# processingModule.net
KiCad netlist of a schematic drawn in Altium Designer
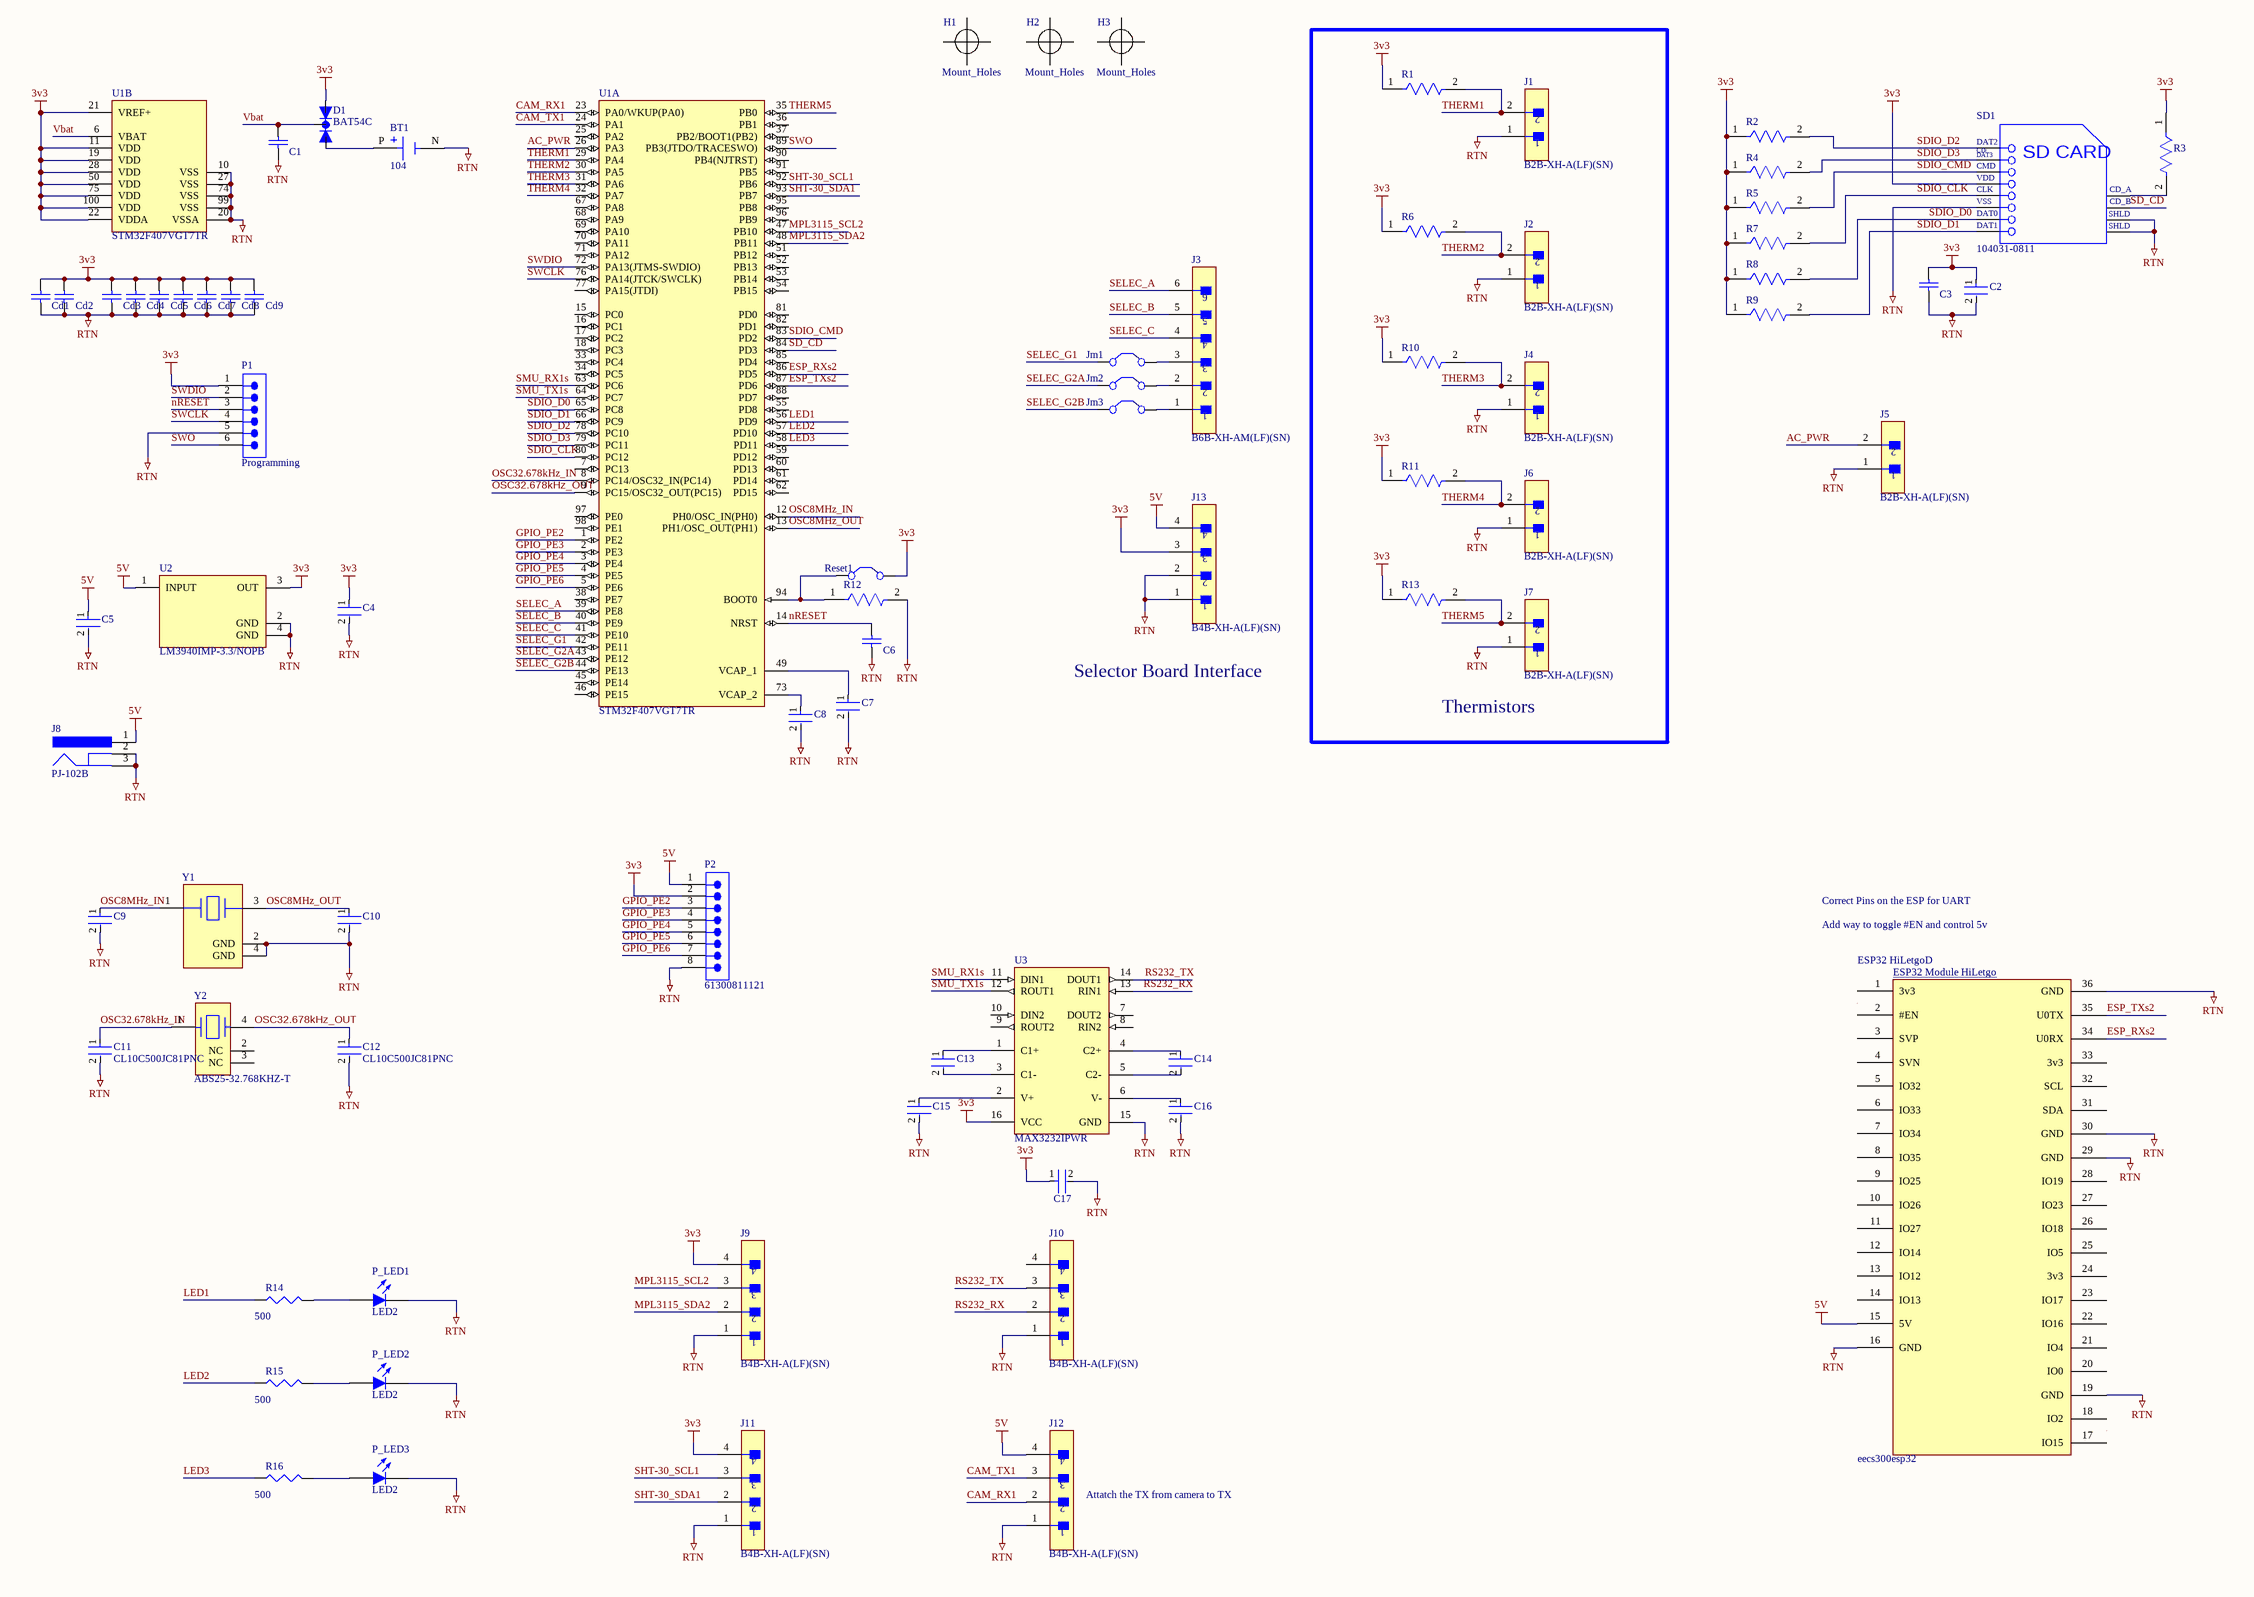
[diagram p0: processingModule.SchDoc]

(export (version "E")
  (design (tool "Eeschema 10.0.6"))
  (components
    (comp (ref "BT1") (value "104") (footprint "BAT_104") (libsource (lib "104") (part "104")))
    (comp (ref "C1")
      (value "CAP 10uF 10V 0603(1608)")
      (footprint "CAPC0603(1608)100_N")
      (description "CAP 10uF 10V ±10% 0603 (1608 Metric) Thickness 1mm SMD")
      (fields (field (name "TOLERANCE") "±10%"))
      (libsource (lib "Altium Content Vault") (part "CMP-1035-02799-1"))
    )
    (comp (ref "C2")
      (value "C0603X104K5RACTU")
      (footprint "FP-C0603-CJ-MFG")
      (description "CAP CER 0.1UF 50V X7R 0603")
      (fields (field (name "VOLTAGE") "50V") (field (name "MANUFACTURER") "Kemet"))
      (libsource (lib "Altium Content Vault") (part "11868f565c42a9108669ba33697ecf6"))
    )
    (comp (ref "C3")
      (value "CAP 10uF 10V 0603(1608)")
      (footprint "CAPC0603(1608)100_N")
      (description "CAP 10uF 10V ±10% 0603 (1608 Metric) Thickness 1mm SMD")
      (fields (field (name "TOLERANCE") "±10%"))
      (libsource (lib "Altium Content Vault") (part "CMP-1035-02799-1"))
    )
    (comp (ref "C4")
      (value "C2012X5R1A336M125AC")
      (footprint "FP-C2012-125-0_2-IPC_A")
      (description "Multilayer Ceramic Capacitors 33μF ±20% 10V X5R SMD 0805")
      (fields (field (name "TOLERANCE") "20%"))
      (libsource (lib "Altium Content Vault") (part "b4654b650e69147ec39a6b967a45e02"))
    )
    (comp (ref "C5")
      (value "GRM188R71C474KA88D")
      (footprint "FP-GRM188-0_1-e0_2_0_5-IPC_A")
      (description "Chip Multilayer Ceramic Capacitors for General Purpose, 0603, 0.47uF, X7R, 15%, 10%, 16V")
      (fields (field (name "VOLTAGE") "16V") (field (name "TOLERANCE") "10%"))
      (libsource (lib "Altium Content Vault") (part "11868f565c42a9108669ba33697ecf6"))
    )
    (comp (ref "C6")
      (value "CAP 100nF 16V 0603(1608)")
      (footprint "CAPC0603(1608)100_N")
      (description "CAP 100nF 16V ±5% 0603 (1608 Metric) Thickness 1mm SMD")
      (fields (field (name "TOLERANCE") "±5%"))
      (libsource (lib "Altium Content Vault") (part "CMP-1035-02583-1"))
    )
    (comp (ref "C7")
      (value "C0603C225K4PACTU")
      (footprint "FP-C0603C225K4PACTU-MFG")
      (description "CAP CER 2.2UF 16V X5R 0603")
      (fields (field (name "TOLERANCE") "10%") (field (name "VOLTAGE") "16V"))
      (libsource (lib "Altium Content Vault") (part "b4654b650e69147ec39a6b967a45e02"))
    )
    (comp (ref "C8")
      (value "C0603C225K4PACTU")
      (footprint "FP-C0603C225K4PACTU-MFG")
      (description "CAP CER 2.2UF 16V X5R 0603")
      (fields (field (name "TOLERANCE") "10%") (field (name "VOLTAGE") "16V"))
      (libsource (lib "Altium Content Vault") (part "b4654b650e69147ec39a6b967a45e02"))
    )
    (comp (ref "C9")
      (value "C0603C200J5GACTU")
      (footprint "FP-C0603C-CF-MFG")
      (description "CAP CER 20PF 50V 5% NP0 0603")
      (fields
        (field (name "MANUFACTURER") "KEMET")
        (field (name "OCTOPART") "https://octopart.com/c0603c200j5gactu-kemet-9138585")
      )
      (libsource (lib "Altium Content Vault") (part "b4654b650e69147ec39a6b967a45e02"))
    )
    (comp (ref "C10")
      (value "C0603C200J5GACTU")
      (footprint "FP-C0603C-CF-MFG")
      (description "CAP CER 20PF 50V 5% NP0 0603")
      (fields
        (field (name "MANUFACTURER") "KEMET")
        (field (name "OCTOPART") "https://octopart.com/c0603c200j5gactu-kemet-9138585")
      )
      (libsource (lib "Altium Content Vault") (part "b4654b650e69147ec39a6b967a45e02"))
    )
    (comp (ref "C11")
      (value "CL10C500JC81PNC")
      (footprint "FP-CL10-IPC_B")
      (description "Cap Ceramic 50pF 100V C0G ±5% Pad SMD 0603 +125°C T/R")
      (fields (field (name "TOLERANCE") "5%"))
      (libsource (lib "Altium Content Vault") (part "b4654b650e69147ec39a6b967a45e02"))
    )
    (comp (ref "C12")
      (value "CL10C500JC81PNC")
      (footprint "FP-CL10-IPC_B")
      (description "Cap Ceramic 50pF 100V C0G ±5% Pad SMD 0603 +125°C T/R")
      (fields (field (name "TOLERANCE") "5%"))
      (libsource (lib "Altium Content Vault") (part "b4654b650e69147ec39a6b967a45e02"))
    )
    (comp (ref "C13")
      (value "C0603X104K5RACTU")
      (footprint "FP-C0603-CJ-MFG")
      (description "CAP CER 0.1UF 50V X7R 0603")
      (fields (field (name "VOLTAGE") "50V") (field (name "MANUFACTURER") "Kemet"))
      (libsource (lib "Altium Content Vault") (part "11868f565c42a9108669ba33697ecf6"))
    )
    (comp (ref "C14")
      (value "C0603X104K5RACTU")
      (footprint "FP-C0603-CJ-MFG")
      (description "CAP CER 0.1UF 50V X7R 0603")
      (fields (field (name "VOLTAGE") "50V") (field (name "MANUFACTURER") "Kemet"))
      (libsource (lib "Altium Content Vault") (part "11868f565c42a9108669ba33697ecf6"))
    )
    (comp (ref "C15")
      (value "C0603X104K5RACTU")
      (footprint "FP-C0603-CJ-MFG")
      (description "CAP CER 0.1UF 50V X7R 0603")
      (fields (field (name "VOLTAGE") "50V") (field (name "MANUFACTURER") "Kemet"))
      (libsource (lib "Altium Content Vault") (part "11868f565c42a9108669ba33697ecf6"))
    )
    (comp (ref "C16")
      (value "C0603X104K5RACTU")
      (footprint "FP-C0603-CJ-MFG")
      (description "CAP CER 0.1UF 50V X7R 0603")
      (fields (field (name "VOLTAGE") "50V") (field (name "MANUFACTURER") "Kemet"))
      (libsource (lib "Altium Content Vault") (part "11868f565c42a9108669ba33697ecf6"))
    )
    (comp (ref "C17")
      (value "C0603X104K5RACTU")
      (footprint "FP-C0603-CJ-MFG")
      (description "CAP CER 0.1UF 50V X7R 0603")
      (fields (field (name "VOLTAGE") "50V") (field (name "MANUFACTURER") "Kemet"))
      (libsource (lib "Altium Content Vault") (part "11868f565c42a9108669ba33697ecf6"))
    )
    (comp (ref "Cd1")
      (value "CAP 10uF 10V 0603(1608)")
      (footprint "CAPC0603(1608)100_N")
      (description "CAP 10uF 10V ±10% 0603 (1608 Metric) Thickness 1mm SMD")
      (fields (field (name "TOLERANCE") "±10%"))
      (libsource (lib "Altium Content Vault") (part "CMP-1035-02799-1"))
    )
    (comp (ref "Cd2")
      (value "CAP 10uF 10V 0603(1608)")
      (footprint "CAPC0603(1608)100_N")
      (description "CAP 10uF 10V ±10% 0603 (1608 Metric) Thickness 1mm SMD")
      (fields (field (name "TOLERANCE") "±10%"))
      (libsource (lib "Altium Content Vault") (part "CMP-1035-02799-1"))
    )
    (comp (ref "Cd3")
      (value "CAP 100nF 16V 0603(1608)")
      (footprint "CAPC0603(1608)100_N")
      (description "CAP 100nF 16V ±5% 0603 (1608 Metric) Thickness 1mm SMD")
      (fields (field (name "TOLERANCE") "±5%"))
      (libsource (lib "Altium Content Vault") (part "CMP-1035-02583-1"))
    )
    (comp (ref "Cd4")
      (value "CAP 100nF 16V 0603(1608)")
      (footprint "CAPC0603(1608)100_N")
      (description "CAP 100nF 16V ±5% 0603 (1608 Metric) Thickness 1mm SMD")
      (fields (field (name "TOLERANCE") "±5%"))
      (libsource (lib "Altium Content Vault") (part "CMP-1035-02583-1"))
    )
    (comp (ref "Cd5")
      (value "CAP 100nF 16V 0603(1608)")
      (footprint "CAPC0603(1608)100_N")
      (description "CAP 100nF 16V ±5% 0603 (1608 Metric) Thickness 1mm SMD")
      (fields (field (name "TOLERANCE") "±5%"))
      (libsource (lib "Altium Content Vault") (part "CMP-1035-02583-1"))
    )
    (comp (ref "Cd6")
      (value "CAP 100nF 16V 0603(1608)")
      (footprint "CAPC0603(1608)100_N")
      (description "CAP 100nF 16V ±5% 0603 (1608 Metric) Thickness 1mm SMD")
      (fields (field (name "TOLERANCE") "±5%"))
      (libsource (lib "Altium Content Vault") (part "CMP-1035-02583-1"))
    )
    (comp (ref "Cd7")
      (value "CAP 100nF 16V 0603(1608)")
      (footprint "CAPC0603(1608)100_N")
      (description "CAP 100nF 16V ±5% 0603 (1608 Metric) Thickness 1mm SMD")
      (fields (field (name "TOLERANCE") "±5%"))
      (libsource (lib "Altium Content Vault") (part "CMP-1035-02583-1"))
    )
    (comp (ref "Cd8")
      (value "CAP 100nF 16V 0603(1608)")
      (footprint "CAPC0603(1608)100_N")
      (description "CAP 100nF 16V ±5% 0603 (1608 Metric) Thickness 1mm SMD")
      (fields (field (name "TOLERANCE") "±5%"))
      (libsource (lib "Altium Content Vault") (part "CMP-1035-02583-1"))
    )
    (comp (ref "Cd9")
      (value "CAP 100nF 16V 0603(1608)")
      (footprint "CAPC0603(1608)100_N")
      (description "CAP 100nF 16V ±5% 0603 (1608 Metric) Thickness 1mm SMD")
      (fields (field (name "TOLERANCE") "±5%"))
      (libsource (lib "Altium Content Vault") (part "CMP-1035-02583-1"))
    )
    (comp (ref "D1")
      (value "BAT54C")
      (footprint "SOT23-R")
      (fields (field (name "MF") "ON Semiconductor"))
      (libsource (lib "BAT54C") (part "BAT54C"))
    )
    (comp (ref "ESP32 HiLetgo")
      (value "eecs300esp32")
      (footprint "eecs300esp32-Footprint-1")
      (description "HiLetgo ESP32 knock off")
      (libsource (lib "esp32") (part "CMP-001-0002-3"))
    )
    (comp (ref "H1")
      (value "Mount_Holes")
      (footprint "MountHole-4-40PTH")
      (libsource (lib "SolarCar") (part "Mount_Holes"))
    )
    (comp (ref "H2")
      (value "Mount_Holes")
      (footprint "MountHole-4-40PTH")
      (libsource (lib "SolarCar") (part "Mount_Holes"))
    )
    (comp (ref "H3")
      (value "Mount_Holes")
      (footprint "MountHole-4-40PTH")
      (libsource (lib "SolarCar") (part "Mount_Holes"))
    )
    (comp (ref "J1")
      (value "B2B-XH-A(LF)(SN)")
      (footprint "FP-B2B-XH-A_LF_SN-MFG")
      (description "CONN HEADER VERT 2POS 2.5MM")
      (libsource (lib "Altium Content Vault") (part "3bc925449376181038e59eaffc5286c"))
    )
    (comp (ref "J2")
      (value "B2B-XH-A(LF)(SN)")
      (footprint "FP-B2B-XH-A_LF_SN-MFG")
      (description "CONN HEADER VERT 2POS 2.5MM")
      (libsource (lib "Altium Content Vault") (part "3bc925449376181038e59eaffc5286c"))
    )
    (comp (ref "J3")
      (value "B6B-XH-AM(LF)(SN)")
      (footprint "FP-B6B-XH-AM_LF_SN-MFG")
      (description "CONN HEADER VERT 6POS 2.5MM")
      (libsource (lib "Altium Content Vault") (part "f2cb566baf1c37ab5a3b8e90bbeafd6"))
    )
    (comp (ref "J4")
      (value "B2B-XH-A(LF)(SN)")
      (footprint "FP-B2B-XH-A_LF_SN-MFG")
      (description "CONN HEADER VERT 2POS 2.5MM")
      (libsource (lib "Altium Content Vault") (part "3bc925449376181038e59eaffc5286c"))
    )
    (comp (ref "J5")
      (value "B2B-XH-A(LF)(SN)")
      (footprint "FP-B2B-XH-A_LF_SN-MFG")
      (description "CONN HEADER VERT 2POS 2.5MM")
      (libsource (lib "Altium Content Vault") (part "3bc925449376181038e59eaffc5286c"))
    )
    (comp (ref "J6")
      (value "B2B-XH-A(LF)(SN)")
      (footprint "FP-B2B-XH-A_LF_SN-MFG")
      (description "CONN HEADER VERT 2POS 2.5MM")
      (libsource (lib "Altium Content Vault") (part "3bc925449376181038e59eaffc5286c"))
    )
    (comp (ref "J7")
      (value "B2B-XH-A(LF)(SN)")
      (footprint "FP-B2B-XH-A_LF_SN-MFG")
      (description "CONN HEADER VERT 2POS 2.5MM")
      (libsource (lib "Altium Content Vault") (part "3bc925449376181038e59eaffc5286c"))
    )
    (comp (ref "J8")
      (value "PJ-102B")
      (footprint "CUI-PJ-102B_V")
      (fields (field (name "MANUFACTURER") "CUIInc."))
      (libsource (lib "Altium Content Vault") (part "JACK-2CD3-RN"))
    )
    (comp (ref "J9")
      (value "B4B-XH-A(LF)(SN)")
      (footprint "FP-B4B-XH-A_LF_SN-MFG")
      (description "CONN HEADER VERT 4POS 2.5MM")
      (libsource (lib "Altium Content Vault") (part "299a8cea1bdcbc3624fe62c390fa72c"))
    )
    (comp (ref "J10")
      (value "B4B-XH-A(LF)(SN)")
      (footprint "FP-B4B-XH-A_LF_SN-MFG")
      (description "CONN HEADER VERT 4POS 2.5MM")
      (libsource (lib "Altium Content Vault") (part "299a8cea1bdcbc3624fe62c390fa72c"))
    )
    (comp (ref "J11")
      (value "B4B-XH-A(LF)(SN)")
      (footprint "FP-B4B-XH-A_LF_SN-MFG")
      (description "CONN HEADER VERT 4POS 2.5MM")
      (libsource (lib "Altium Content Vault") (part "299a8cea1bdcbc3624fe62c390fa72c"))
    )
    (comp (ref "J12")
      (value "B4B-XH-A(LF)(SN)")
      (footprint "FP-B4B-XH-A_LF_SN-MFG")
      (description "CONN HEADER VERT 4POS 2.5MM")
      (libsource (lib "Altium Content Vault") (part "299a8cea1bdcbc3624fe62c390fa72c"))
    )
    (comp (ref "J13")
      (value "B4B-XH-A(LF)(SN)")
      (footprint "FP-B4B-XH-A_LF_SN-MFG")
      (description "CONN HEADER VERT 4POS 2.5MM")
      (libsource (lib "Altium Content Vault") (part "299a8cea1bdcbc3624fe62c390fa72c"))
    )
    (comp (ref "Jm1")
      (value "SolderJumper")
      (footprint "bridge")
      (description "Solder Configuration Jumper")
      (fields (field (name "PUBLISHER") "Altium Limited"))
      (libsource (lib "SolarCar") (part "SolderJumper"))
    )
    (comp (ref "Jm2")
      (value "SolderJumper")
      (footprint "bridge")
      (description "Solder Configuration Jumper")
      (fields (field (name "PUBLISHER") "Altium Limited"))
      (libsource (lib "SolarCar") (part "SolderJumper"))
    )
    (comp (ref "Jm3")
      (value "SolderJumper")
      (footprint "bridge")
      (description "Solder Configuration Jumper")
      (fields (field (name "PUBLISHER") "Altium Limited"))
      (libsource (lib "SolarCar") (part "SolderJumper"))
    )
    (comp (ref "P1")
      (value "Programming")
      (footprint "61300611121")
      (libsource (lib "Altium Content Vault") (part "Header_Male_1R_06P"))
    )
    (comp (ref "P2")
      (value "61300811121")
      (footprint "61300811121")
      (libsource (lib "Altium Content Vault") (part "Header_Male_1R_08P"))
    )
    (comp (ref "P_LED1")
      (value "LED2")
      (footprint "LED0805")
      (description "Typical RED, GREEN, YELLOW, AMBER GaAs LED")
      (fields (field (name "PUBLISHER") "Altium Limited"))
      (libsource (lib "University of Michigan Solar Car Team") (part "LED2"))
    )
    (comp (ref "P_LED2")
      (value "LED2")
      (footprint "LED0805")
      (description "Typical RED, GREEN, YELLOW, AMBER GaAs LED")
      (fields (field (name "PUBLISHER") "Altium Limited"))
      (libsource (lib "University of Michigan Solar Car Team") (part "LED2"))
    )
    (comp (ref "P_LED3")
      (value "LED2")
      (footprint "LED0805")
      (description "Typical RED, GREEN, YELLOW, AMBER GaAs LED")
      (fields (field (name "PUBLISHER") "Altium Limited"))
      (libsource (lib "University of Michigan Solar Car Team") (part "LED2"))
    )
    (comp (ref "R1")
      (value "RC0603FR-0710KL")
      (footprint "FP-RC0603-0_55-IPC_C")
      (description "RES 10K OHM 1% 1/10W 0603")
      (fields (field (name "TOLERANCE") "1%"))
      (libsource (lib "Altium Content Vault") (part "1029c3af85768c4190bb7ad29bc67b5"))
    )
    (comp (ref "R2")
      (value "RC0603FR-0747KL")
      (footprint "FP-RC0603FR-0747KL-MFG")
      (description "RES SMD 47K OHM 1% 1/10W 0603")
      (fields (field (name "TOLERANCE") "1%"))
      (libsource (lib "Altium Content Vault") (part "1029c3af85768c4190bb7ad29bc67b5"))
    )
    (comp (ref "R3")
      (value "RC0603FR-0747KL")
      (footprint "FP-RC0603FR-0747KL-MFG")
      (description "RES SMD 47K OHM 1% 1/10W 0603")
      (fields (field (name "TOLERANCE") "1%"))
      (libsource (lib "Altium Content Vault") (part "1029c3af85768c4190bb7ad29bc67b5"))
    )
    (comp (ref "R4")
      (value "RC0603FR-0747KL")
      (footprint "FP-RC0603FR-0747KL-MFG")
      (description "RES SMD 47K OHM 1% 1/10W 0603")
      (fields (field (name "TOLERANCE") "1%"))
      (libsource (lib "Altium Content Vault") (part "1029c3af85768c4190bb7ad29bc67b5"))
    )
    (comp (ref "R5")
      (value "RC0603FR-0747KL")
      (footprint "FP-RC0603FR-0747KL-MFG")
      (description "RES SMD 47K OHM 1% 1/10W 0603")
      (fields (field (name "TOLERANCE") "1%"))
      (libsource (lib "Altium Content Vault") (part "1029c3af85768c4190bb7ad29bc67b5"))
    )
    (comp (ref "R6")
      (value "RC0603FR-0710KL")
      (footprint "FP-RC0603-0_55-IPC_C")
      (description "RES 10K OHM 1% 1/10W 0603")
      (fields (field (name "TOLERANCE") "1%"))
      (libsource (lib "Altium Content Vault") (part "1029c3af85768c4190bb7ad29bc67b5"))
    )
    (comp (ref "R7")
      (value "RC0603FR-0747KL")
      (footprint "FP-RC0603FR-0747KL-MFG")
      (description "RES SMD 47K OHM 1% 1/10W 0603")
      (fields (field (name "TOLERANCE") "1%"))
      (libsource (lib "Altium Content Vault") (part "1029c3af85768c4190bb7ad29bc67b5"))
    )
    (comp (ref "R8")
      (value "RC0603FR-0747KL")
      (footprint "FP-RC0603FR-0747KL-MFG")
      (description "RES SMD 47K OHM 1% 1/10W 0603")
      (fields (field (name "TOLERANCE") "1%"))
      (libsource (lib "Altium Content Vault") (part "1029c3af85768c4190bb7ad29bc67b5"))
    )
    (comp (ref "R9")
      (value "RC0603FR-0747KL")
      (footprint "FP-RC0603FR-0747KL-MFG")
      (description "RES SMD 47K OHM 1% 1/10W 0603")
      (fields (field (name "TOLERANCE") "1%"))
      (libsource (lib "Altium Content Vault") (part "1029c3af85768c4190bb7ad29bc67b5"))
    )
    (comp (ref "R10")
      (value "RC0603FR-0710KL")
      (footprint "FP-RC0603-0_55-IPC_C")
      (description "RES 10K OHM 1% 1/10W 0603")
      (fields (field (name "TOLERANCE") "1%"))
      (libsource (lib "Altium Content Vault") (part "1029c3af85768c4190bb7ad29bc67b5"))
    )
    (comp (ref "R11")
      (value "RC0603FR-0710KL")
      (footprint "FP-RC0603-0_55-IPC_C")
      (description "RES 10K OHM 1% 1/10W 0603")
      (fields (field (name "TOLERANCE") "1%"))
      (libsource (lib "Altium Content Vault") (part "1029c3af85768c4190bb7ad29bc67b5"))
    )
    (comp (ref "R12")
      (value "RC0603FR-0710KL")
      (footprint "FP-RC0603-0_55-IPC_C")
      (description "RES 10K OHM 1% 1/10W 0603")
      (fields (field (name "TOLERANCE") "1%"))
      (libsource (lib "Altium Content Vault") (part "1029c3af85768c4190bb7ad29bc67b5"))
    )
    (comp (ref "R13")
      (value "RC0603FR-0710KL")
      (footprint "FP-RC0603-0_55-IPC_C")
      (description "RES 10K OHM 1% 1/10W 0603")
      (fields (field (name "TOLERANCE") "1%"))
      (libsource (lib "Altium Content Vault") (part "1029c3af85768c4190bb7ad29bc67b5"))
    )
    (comp (ref "R14")
      (value "500")
      (footprint "J1-0603")
      (description "Resistor")
      (fields (field (name "PUBLISHER") "Altium Limited"))
      (libsource (lib "SolarCar") (part "Res3"))
    )
    (comp (ref "R15")
      (value "500")
      (footprint "J1-0603")
      (description "Resistor")
      (fields (field (name "PUBLISHER") "Altium Limited"))
      (libsource (lib "SolarCar") (part "Res3"))
    )
    (comp (ref "R16")
      (value "500")
      (footprint "J1-0603")
      (description "Resistor")
      (fields (field (name "PUBLISHER") "Altium Limited"))
      (libsource (lib "SolarCar") (part "Res3"))
    )
    (comp (ref "Reset1")
      (value "SolderJumper")
      (footprint "bridge")
      (description "Solder Configuration Jumper")
      (fields (field (name "PUBLISHER") "Altium Limited"))
      (libsource (lib "SolarCar") (part "SolderJumper"))
    )
    (comp (ref "SD1")
      (value "104031-0811")
      (footprint "MOLX-104031-0811_V")
      (description "Micro SD Card, RA, -25 to 85 degC, 8-Pin SMD, RoHS, Tape and Reel")
      (fields (field (name "MANUFACTURER") "Molex"))
      (libsource (lib "Altium Content Vault") (part "CN-SD-8-2SW-2S"))
    )
    (comp (ref "U1")
      (value "STM32F407VGT7TR")
      (footprint "STM-LQFP100_L")
      (libsource (lib "Altium Content Vault") (part "MC-ARM-STM32F4XX-LQFP100"))
    )
    (comp (ref "U2")
      (value "LM3940IMP-3.3/NOPB")
      (footprint "FP-DCY0004A-MFG")
      (description "IC REG LINEAR 3.3V 1A SOT223-4")
      (libsource (lib "Altium Content Vault") (part "ef78896361455d16e3252a05c23564e"))
    )
    (comp (ref "U3")
      (value "MAX3232IPWR")
      (footprint "PW0016A_N")
      (libsource (lib "Altium Content Vault") (part "TI-MAX3232-TSSOP_PW-16"))
    )
    (comp (ref "Y1")
      (value "ABM3B-8.000MHZ-10-D-1-G-T")
      (footprint "FP-ABM3B-MFG")
      (description "Crystal 8MHz ±10ppm 10pF SMD-4 5mm x 3.2mm")
      (libsource (lib "Altium Content Vault") (part "48e526d86b7f2615d98721063c72f49"))
    )
    (comp (ref "Y2")
      (value "ABS25-32.768KHZ-T")
      (footprint "FP-ABS25-MFG")
      (description "CRYSTAL 32.7680KHZ 12.5PF SMD")
      (fields (field (name "TOLERANCE") "20ppm"))
      (libsource (lib "Altium Content Vault") (part "d2378e42ab3755ffcd472789242ec61"))
    )
  )
  (nets
    (net (code "1") (name "/AC_PWR") (class "Default")
      (node (ref "J5") (pin "2") (pinfunction "2_2") (pintype "passive"))
      (node (ref "U1") (pin "26") (pinfunction "PA3_26") (pintype "bidirectional"))
    )
    (net (code "2") (name "/CAM_RX1") (class "Default")
      (node (ref "J12") (pin "2") (pinfunction "2_2") (pintype "passive"))
      (node (ref "U1") (pin "23") (pinfunction "PA0/WKUP(PA0)_23") (pintype "bidirectional"))
    )
    (net (code "3") (name "/CAM_TX1") (class "Default")
      (node (ref "J12") (pin "3") (pinfunction "3_3") (pintype "passive"))
      (node (ref "U1") (pin "24") (pinfunction "PA1_24") (pintype "bidirectional"))
    )
    (net (code "4") (name "/ESP_RXs2") (class "Default")
      (node (ref "ESP32 HiLetgo") (pin "34") (pinfunction "U0RX_34") (pintype "passive"))
      (node (ref "U1") (pin "86") (pinfunction "PD5_86") (pintype "bidirectional"))
    )
    (net (code "5") (name "/ESP_TXs2") (class "Default")
      (node (ref "ESP32 HiLetgo") (pin "35") (pinfunction "U0TX_35") (pintype "passive"))
      (node (ref "U1") (pin "87") (pinfunction "PD6_87") (pintype "bidirectional"))
    )
    (net (code "6") (name "/GPIO_PE2") (class "Default")
      (node (ref "P2") (pin "3") (pinfunction "3_3") (pintype "passive"))
      (node (ref "U1") (pin "1") (pinfunction "PE2_1") (pintype "bidirectional"))
    )
    (net (code "7") (name "/GPIO_PE3") (class "Default")
      (node (ref "P2") (pin "4") (pinfunction "4_4") (pintype "passive"))
      (node (ref "U1") (pin "2") (pinfunction "PE3_2") (pintype "bidirectional"))
    )
    (net (code "8") (name "/GPIO_PE4") (class "Default")
      (node (ref "P2") (pin "5") (pinfunction "5_5") (pintype "passive"))
      (node (ref "U1") (pin "3") (pinfunction "PE4_3") (pintype "bidirectional"))
    )
    (net (code "9") (name "/GPIO_PE5") (class "Default")
      (node (ref "P2") (pin "6") (pinfunction "6_6") (pintype "passive"))
      (node (ref "U1") (pin "4") (pinfunction "PE5_4") (pintype "bidirectional"))
    )
    (net (code "10") (name "/GPIO_PE6") (class "Default")
      (node (ref "P2") (pin "7") (pinfunction "7_7") (pintype "passive"))
      (node (ref "U1") (pin "5") (pinfunction "PE6_5") (pintype "bidirectional"))
    )
    (net (code "11") (name "/LED1") (class "Default")
      (node (ref "R14") (pin "1") (pinfunction "1_1") (pintype "passive"))
      (node (ref "U1") (pin "56") (pinfunction "PD9_56") (pintype "bidirectional"))
    )
    (net (code "12") (name "/LED2") (class "Default")
      (node (ref "R15") (pin "1") (pinfunction "1_1") (pintype "passive"))
      (node (ref "U1") (pin "57") (pinfunction "PD10_57") (pintype "bidirectional"))
    )
    (net (code "13") (name "/LED3") (class "Default")
      (node (ref "R16") (pin "1") (pinfunction "1_1") (pintype "passive"))
      (node (ref "U1") (pin "58") (pinfunction "PD11_58") (pintype "bidirectional"))
    )
    (net (code "14") (name "/MPL3115_SCL2") (class "Default")
      (node (ref "J9") (pin "3") (pinfunction "3_3") (pintype "passive"))
      (node (ref "U1") (pin "47") (pinfunction "PB10_47") (pintype "bidirectional"))
    )
    (net (code "15") (name "/MPL3115_SDA2") (class "Default")
      (node (ref "J9") (pin "2") (pinfunction "2_2") (pintype "passive"))
      (node (ref "U1") (pin "48") (pinfunction "PB11_48") (pintype "bidirectional"))
    )
    (net (code "16") (name "/OSC8MHz_IN") (class "Default")
      (node (ref "C9") (pin "1") (pinfunction "1_1") (pintype "passive"))
      (node (ref "U1") (pin "12") (pinfunction "PH0/OSC_IN(PH0)_12") (pintype "bidirectional"))
      (node (ref "Y1") (pin "1") (pinfunction "1_1") (pintype "passive"))
    )
    (net (code "17") (name "/OSC8MHz_OUT") (class "Default")
      (node (ref "C10") (pin "1") (pinfunction "1_1") (pintype "passive"))
      (node (ref "U1") (pin "13") (pinfunction "PH1/OSC_OUT(PH1)_13") (pintype "bidirectional"))
      (node (ref "Y1") (pin "3") (pinfunction "3_3") (pintype "passive"))
    )
    (net (code "18") (name "/OSC32.678kHz_IN") (class "Default")
      (node (ref "C11") (pin "1") (pinfunction "1_1") (pintype "passive"))
      (node (ref "U1") (pin "8") (pinfunction "PC14/OSC32_IN(PC14)_8") (pintype "bidirectional"))
      (node (ref "Y2") (pin "1") (pinfunction "1_1") (pintype "passive"))
    )
    (net (code "19") (name "/OSC32.678kHz_OUT") (class "Default")
      (node (ref "C12") (pin "1") (pinfunction "1_1") (pintype "passive"))
      (node (ref "U1") (pin "9") (pinfunction "PC15/OSC32_OUT(PC15)_9") (pintype "bidirectional"))
      (node (ref "Y2") (pin "4") (pinfunction "4_4") (pintype "passive"))
    )
    (net (code "20") (name "/RS232_RX") (class "Default")
      (node (ref "J10") (pin "2") (pinfunction "2_2") (pintype "passive"))
      (node (ref "U3") (pin "13") (pinfunction "RIN1_13") (pintype "input"))
    )
    (net (code "21") (name "/RS232_TX") (class "Default")
      (node (ref "J10") (pin "3") (pinfunction "3_3") (pintype "passive"))
      (node (ref "U3") (pin "14") (pinfunction "DOUT1_14") (pintype "output"))
    )
    (net (code "22") (name "/SDIO_CLK") (class "Default")
      (node (ref "R7") (pin "2") (pinfunction "2_2") (pintype "passive"))
      (node (ref "SD1") (pin "5") (pinfunction "CLK_5") (pintype "passive"))
      (node (ref "U1") (pin "80") (pinfunction "PC12_80") (pintype "bidirectional"))
    )
    (net (code "23") (name "/SDIO_CMD") (class "Default")
      (node (ref "R5") (pin "2") (pinfunction "2_2") (pintype "passive"))
      (node (ref "SD1") (pin "3") (pinfunction "VSS1_3") (pintype "passive"))
      (node (ref "U1") (pin "83") (pinfunction "PD2_83") (pintype "bidirectional"))
    )
    (net (code "24") (name "/SDIO_D0") (class "Default")
      (node (ref "R8") (pin "2") (pinfunction "2_2") (pintype "passive"))
      (node (ref "SD1") (pin "7") (pinfunction "DAT0_7") (pintype "passive"))
      (node (ref "U1") (pin "65") (pinfunction "PC8_65") (pintype "bidirectional"))
    )
    (net (code "25") (name "/SDIO_D1") (class "Default")
      (node (ref "R9") (pin "2") (pinfunction "2_2") (pintype "passive"))
      (node (ref "SD1") (pin "8") (pinfunction "DAT1_8") (pintype "passive"))
      (node (ref "U1") (pin "66") (pinfunction "PC9_66") (pintype "bidirectional"))
    )
    (net (code "26") (name "/SDIO_D2") (class "Default")
      (node (ref "R2") (pin "2") (pinfunction "2_2") (pintype "passive"))
      (node (ref "SD1") (pin "1") (pinfunction "CD/DAT3_1") (pintype "passive"))
      (node (ref "U1") (pin "78") (pinfunction "PC10_78") (pintype "bidirectional"))
    )
    (net (code "27") (name "/SDIO_D3") (class "Default")
      (node (ref "R4") (pin "2") (pinfunction "2_2") (pintype "passive"))
      (node (ref "SD1") (pin "2") (pinfunction "CMD_2") (pintype "passive"))
      (node (ref "U1") (pin "79") (pinfunction "PC11_79") (pintype "bidirectional"))
    )
    (net (code "28") (name "/SD_CD") (class "Default")
      (node (ref "SD1") (pin "10") (pinfunction "CD_B_10") (pintype "passive"))
      (node (ref "U1") (pin "84") (pinfunction "PD3_84") (pintype "bidirectional"))
    )
    (net (code "29") (name "/SELEC_A") (class "Default")
      (node (ref "J3") (pin "6") (pinfunction "6_6") (pintype "passive"))
      (node (ref "U1") (pin "39") (pinfunction "PE8_39") (pintype "bidirectional"))
    )
    (net (code "30") (name "/SELEC_B") (class "Default")
      (node (ref "J3") (pin "5") (pinfunction "5_5") (pintype "passive"))
      (node (ref "U1") (pin "40") (pinfunction "PE9_40") (pintype "bidirectional"))
    )
    (net (code "31") (name "/SELEC_C") (class "Default")
      (node (ref "J3") (pin "4") (pinfunction "4_4") (pintype "passive"))
      (node (ref "U1") (pin "41") (pinfunction "PE10_41") (pintype "bidirectional"))
    )
    (net (code "32") (name "/SELEC_G1") (class "Default")
      (node (ref "Jm1") (pin "1") (pinfunction "C1_1") (pintype "passive"))
      (node (ref "U1") (pin "42") (pinfunction "PE11_42") (pintype "bidirectional"))
    )
    (net (code "33") (name "/SELEC_G2A") (class "Default")
      (node (ref "Jm2") (pin "1") (pinfunction "C1_1") (pintype "passive"))
      (node (ref "U1") (pin "43") (pinfunction "PE12_43") (pintype "bidirectional"))
    )
    (net (code "34") (name "/SELEC_G2B") (class "Default")
      (node (ref "Jm3") (pin "1") (pinfunction "C1_1") (pintype "passive"))
      (node (ref "U1") (pin "44") (pinfunction "PE13_44") (pintype "bidirectional"))
    )
    (net (code "35") (name "/SHT-30_SCL1") (class "Default")
      (node (ref "J11") (pin "3") (pinfunction "3_3") (pintype "passive"))
      (node (ref "U1") (pin "92") (pinfunction "PB6_92") (pintype "bidirectional"))
    )
    (net (code "36") (name "/SHT-30_SDA1") (class "Default")
      (node (ref "J11") (pin "2") (pinfunction "2_2") (pintype "passive"))
      (node (ref "U1") (pin "93") (pinfunction "PB7_93") (pintype "bidirectional"))
    )
    (net (code "37") (name "/SMU_RX1s") (class "Default")
      (node (ref "U1") (pin "63") (pinfunction "PC6_63") (pintype "bidirectional"))
      (node (ref "U3") (pin "11") (pinfunction "DIN1_11") (pintype "input"))
    )
    (net (code "38") (name "/SMU_TX1s") (class "Default")
      (node (ref "U1") (pin "64") (pinfunction "PC7_64") (pintype "bidirectional"))
      (node (ref "U3") (pin "12") (pinfunction "ROUT1_12") (pintype "output"))
    )
    (net (code "39") (name "/SWCLK") (class "Default")
      (node (ref "P1") (pin "4") (pinfunction "4_4") (pintype "passive"))
      (node (ref "U1") (pin "76") (pinfunction "PA14(JTCK/SWCLK)_76") (pintype "bidirectional"))
    )
    (net (code "40") (name "/SWDIO") (class "Default")
      (node (ref "P1") (pin "2") (pinfunction "2_2") (pintype "passive"))
      (node (ref "U1") (pin "72") (pinfunction "PA13(JTMS-SWDIO)_72") (pintype "bidirectional"))
    )
    (net (code "41") (name "/SWO") (class "Default")
      (node (ref "P1") (pin "6") (pinfunction "6_6") (pintype "passive"))
      (node (ref "U1") (pin "89") (pinfunction "PB3(JTDO/TRACESWO)_89") (pintype "bidirectional"))
    )
    (net (code "42") (name "/THERM1") (class "Default")
      (node (ref "J1") (pin "2") (pinfunction "2_2") (pintype "passive"))
      (node (ref "R1") (pin "2") (pinfunction "2_2") (pintype "passive"))
      (node (ref "U1") (pin "29") (pinfunction "PA4_29") (pintype "bidirectional"))
    )
    (net (code "43") (name "/THERM2") (class "Default")
      (node (ref "J2") (pin "2") (pinfunction "2_2") (pintype "passive"))
      (node (ref "R6") (pin "2") (pinfunction "2_2") (pintype "passive"))
      (node (ref "U1") (pin "30") (pinfunction "PA5_30") (pintype "bidirectional"))
    )
    (net (code "44") (name "/THERM3") (class "Default")
      (node (ref "J4") (pin "2") (pinfunction "2_2") (pintype "passive"))
      (node (ref "R10") (pin "2") (pinfunction "2_2") (pintype "passive"))
      (node (ref "U1") (pin "31") (pinfunction "PA6_31") (pintype "bidirectional"))
    )
    (net (code "45") (name "/THERM4") (class "Default")
      (node (ref "J6") (pin "2") (pinfunction "2_2") (pintype "passive"))
      (node (ref "R11") (pin "2") (pinfunction "2_2") (pintype "passive"))
      (node (ref "U1") (pin "32") (pinfunction "PA7_32") (pintype "bidirectional"))
    )
    (net (code "46") (name "/THERM5") (class "Default")
      (node (ref "J7") (pin "2") (pinfunction "2_2") (pintype "passive"))
      (node (ref "R13") (pin "2") (pinfunction "2_2") (pintype "passive"))
      (node (ref "U1") (pin "35") (pinfunction "PB0_35") (pintype "bidirectional"))
    )
    (net (code "47") (name "/Vbat") (class "Default")
      (node (ref "C1") (pin "2") (pinfunction "2_2") (pintype "passive"))
      (node (ref "D1") (pin "3") (pinfunction "C_3") (pintype "passive"))
      (node (ref "U1") (pin "6") (pinfunction "VBAT_6") (pintype "power_in"))
    )
    (net (code "48") (name "/nRESET") (class "Default")
      (node (ref "C6") (pin "2") (pinfunction "2_2") (pintype "passive"))
      (node (ref "P1") (pin "3") (pinfunction "3_3") (pintype "passive"))
      (node (ref "U1") (pin "14") (pinfunction "NRST_14") (pintype "bidirectional"))
    )
    (net (code "49") (name "3v3") (class "Default")
      (node (ref "C17") (pin "1") (pinfunction "1_1") (pintype "passive"))
      (node (ref "C2") (pin "1") (pinfunction "1_1") (pintype "passive"))
      (node (ref "C3") (pin "2") (pinfunction "2_2") (pintype "passive"))
      (node (ref "C4") (pin "1") (pinfunction "1_1") (pintype "passive"))
      (node (ref "Cd1") (pin "2") (pinfunction "2_2") (pintype "passive"))
      (node (ref "Cd2") (pin "2") (pinfunction "2_2") (pintype "passive"))
      (node (ref "Cd3") (pin "2") (pinfunction "2_2") (pintype "passive"))
      (node (ref "Cd4") (pin "2") (pinfunction "2_2") (pintype "passive"))
      (node (ref "Cd5") (pin "2") (pinfunction "2_2") (pintype "passive"))
      (node (ref "Cd6") (pin "2") (pinfunction "2_2") (pintype "passive"))
      (node (ref "Cd7") (pin "2") (pinfunction "2_2") (pintype "passive"))
      (node (ref "Cd8") (pin "2") (pinfunction "2_2") (pintype "passive"))
      (node (ref "Cd9") (pin "2") (pinfunction "2_2") (pintype "passive"))
      (node (ref "D1") (pin "2") (pinfunction "A2_2") (pintype "passive"))
      (node (ref "J11") (pin "4") (pinfunction "4_4") (pintype "passive"))
      (node (ref "J13") (pin "3") (pinfunction "3_3") (pintype "passive"))
      (node (ref "J9") (pin "4") (pinfunction "4_4") (pintype "passive"))
      (node (ref "P1") (pin "1") (pinfunction "1_1") (pintype "passive"))
      (node (ref "P2") (pin "2") (pinfunction "2_2") (pintype "passive"))
      (node (ref "R1") (pin "1") (pinfunction "1_1") (pintype "passive"))
      (node (ref "R10") (pin "1") (pinfunction "1_1") (pintype "passive"))
      (node (ref "R11") (pin "1") (pinfunction "1_1") (pintype "passive"))
      (node (ref "R13") (pin "1") (pinfunction "1_1") (pintype "passive"))
      (node (ref "R2") (pin "1") (pinfunction "1_1") (pintype "passive"))
      (node (ref "R3") (pin "1") (pinfunction "1_1") (pintype "passive"))
      (node (ref "R4") (pin "1") (pinfunction "1_1") (pintype "passive"))
      (node (ref "R5") (pin "1") (pinfunction "1_1") (pintype "passive"))
      (node (ref "R6") (pin "1") (pinfunction "1_1") (pintype "passive"))
      (node (ref "R7") (pin "1") (pinfunction "1_1") (pintype "passive"))
      (node (ref "R8") (pin "1") (pinfunction "1_1") (pintype "passive"))
      (node (ref "R9") (pin "1") (pinfunction "1_1") (pintype "passive"))
      (node (ref "Reset1") (pin "2") (pinfunction "C2_2") (pintype "passive"))
      (node (ref "SD1") (pin "4") (pinfunction "VDD_4") (pintype "passive"))
      (node (ref "U1") (pin "100") (pinfunction "VDD_100") (pintype "power_in"))
      (node (ref "U1") (pin "11") (pinfunction "VDD_11") (pintype "power_in"))
      (node (ref "U1") (pin "19") (pinfunction "VDD_19") (pintype "power_in"))
      (node (ref "U1") (pin "21") (pinfunction "VREF+_21") (pintype "power_in"))
      (node (ref "U1") (pin "22") (pinfunction "VDDA_22") (pintype "power_in"))
      (node (ref "U1") (pin "28") (pinfunction "VDD_28") (pintype "power_in"))
      (node (ref "U1") (pin "50") (pinfunction "VDD_50") (pintype "power_in"))
      (node (ref "U1") (pin "75") (pinfunction "VDD_75") (pintype "power_in"))
      (node (ref "U2") (pin "3") (pinfunction "OUT_3") (pintype "power_in"))
      (node (ref "U3") (pin "16") (pinfunction "VCC_16") (pintype "power_in"))
    )
    (net (code "50") (name "5V") (class "Default")
      (node (ref "C5") (pin "1") (pinfunction "1_1") (pintype "passive"))
      (node (ref "ESP32 HiLetgo") (pin "15") (pinfunction "5V_15") (pintype "passive"))
      (node (ref "J12") (pin "4") (pinfunction "4_4") (pintype "passive"))
      (node (ref "J13") (pin "4") (pinfunction "4_4") (pintype "passive"))
      (node (ref "J8") (pin "1") (pinfunction "1_1") (pintype "passive"))
      (node (ref "P2") (pin "1") (pinfunction "1_1") (pintype "passive"))
      (node (ref "U2") (pin "1") (pinfunction "INPUT_1") (pintype "power_in"))
    )
    (net (code "51") (name "Net-(BT1-POS)") (class "Default")
      (node (ref "BT1") (pin "P") (pinfunction "POS_P") (pintype "passive"))
      (node (ref "D1") (pin "1") (pinfunction "A1_1") (pintype "passive"))
    )
    (net (code "52") (name "Net-(Jm1-C2)") (class "Default")
      (node (ref "J3") (pin "3") (pinfunction "3_3") (pintype "passive"))
      (node (ref "Jm1") (pin "2") (pinfunction "C2_2") (pintype "passive"))
    )
    (net (code "53") (name "Net-(Jm2-C2)") (class "Default")
      (node (ref "J3") (pin "2") (pinfunction "2_2") (pintype "passive"))
      (node (ref "Jm2") (pin "2") (pinfunction "C2_2") (pintype "passive"))
    )
    (net (code "54") (name "Net-(Jm3-C2)") (class "Default")
      (node (ref "J3") (pin "1") (pinfunction "1_1") (pintype "passive"))
      (node (ref "Jm3") (pin "2") (pinfunction "C2_2") (pintype "passive"))
    )
    (net (code "55") (name "Net-(P_LED1-A)") (class "Default")
      (node (ref "P_LED1") (pin "1") (pinfunction "A_1") (pintype "passive"))
      (node (ref "R14") (pin "2") (pinfunction "2_2") (pintype "passive"))
    )
    (net (code "56") (name "Net-(P_LED2-A)") (class "Default")
      (node (ref "P_LED2") (pin "1") (pinfunction "A_1") (pintype "passive"))
      (node (ref "R15") (pin "2") (pinfunction "2_2") (pintype "passive"))
    )
    (net (code "57") (name "Net-(P_LED3-A)") (class "Default")
      (node (ref "P_LED3") (pin "1") (pinfunction "A_1") (pintype "passive"))
      (node (ref "R16") (pin "2") (pinfunction "2_2") (pintype "passive"))
    )
    (net (code "58") (name "Net-(Reset1-C1)") (class "Default")
      (node (ref "R12") (pin "1") (pinfunction "1_1") (pintype "passive"))
      (node (ref "Reset1") (pin "1") (pinfunction "C1_1") (pintype "passive"))
      (node (ref "U1") (pin "94") (pinfunction "BOOT0_94") (pintype "input"))
    )
    (net (code "59") (name "Net-(SD1-CD_A)") (class "Default")
      (node (ref "R3") (pin "2") (pinfunction "2_2") (pintype "passive"))
      (node (ref "SD1") (pin "9") (pinfunction "CD_A_9") (pintype "passive"))
    )
    (net (code "60") (name "Net-(U1A-VCAP_1)") (class "Default")
      (node (ref "C7") (pin "1") (pinfunction "1_1") (pintype "passive"))
      (node (ref "U1") (pin "49") (pinfunction "VCAP_1_49") (pintype "passive"))
    )
    (net (code "61") (name "Net-(U1A-VCAP_2)") (class "Default")
      (node (ref "C8") (pin "1") (pinfunction "1_1") (pintype "passive"))
      (node (ref "U1") (pin "73") (pinfunction "VCAP_2_73") (pintype "passive"))
    )
    (net (code "62") (name "Net-(U3-C1+)") (class "Default")
      (node (ref "C13") (pin "1") (pinfunction "1_1") (pintype "passive"))
      (node (ref "U3") (pin "1") (pinfunction "C1+_1") (pintype "passive"))
    )
    (net (code "63") (name "Net-(U3-C1-)") (class "Default")
      (node (ref "C13") (pin "2") (pinfunction "2_2") (pintype "passive"))
      (node (ref "U3") (pin "3") (pinfunction "C1-_3") (pintype "passive"))
    )
    (net (code "64") (name "Net-(U3-C2+)") (class "Default")
      (node (ref "C14") (pin "1") (pinfunction "1_1") (pintype "passive"))
      (node (ref "U3") (pin "4") (pinfunction "C2+_4") (pintype "passive"))
    )
    (net (code "65") (name "Net-(U3-C2-)") (class "Default")
      (node (ref "C14") (pin "2") (pinfunction "2_2") (pintype "passive"))
      (node (ref "U3") (pin "5") (pinfunction "C2-_5") (pintype "passive"))
    )
    (net (code "66") (name "Net-(U3-V+)") (class "Default")
      (node (ref "C15") (pin "1") (pinfunction "1_1") (pintype "passive"))
      (node (ref "U3") (pin "2") (pinfunction "V+_2") (pintype "power_in"))
    )
    (net (code "67") (name "Net-(U3-V-)") (class "Default")
      (node (ref "C16") (pin "1") (pinfunction "1_1") (pintype "passive"))
      (node (ref "U3") (pin "6") (pinfunction "V-_6") (pintype "power_in"))
    )
    (net (code "68") (name "RTN") (class "Default")
      (node (ref "BT1") (pin "N") (pinfunction "NEG_N") (pintype "passive"))
      (node (ref "C1") (pin "1") (pinfunction "1_1") (pintype "passive"))
      (node (ref "C10") (pin "2") (pinfunction "2_2") (pintype "passive"))
      (node (ref "C11") (pin "2") (pinfunction "2_2") (pintype "passive"))
      (node (ref "C12") (pin "2") (pinfunction "2_2") (pintype "passive"))
      (node (ref "C15") (pin "2") (pinfunction "2_2") (pintype "passive"))
      (node (ref "C16") (pin "2") (pinfunction "2_2") (pintype "passive"))
      (node (ref "C17") (pin "2") (pinfunction "2_2") (pintype "passive"))
      (node (ref "C2") (pin "2") (pinfunction "2_2") (pintype "passive"))
      (node (ref "C3") (pin "1") (pinfunction "1_1") (pintype "passive"))
      (node (ref "C4") (pin "2") (pinfunction "2_2") (pintype "passive"))
      (node (ref "C5") (pin "2") (pinfunction "2_2") (pintype "passive"))
      (node (ref "C6") (pin "1") (pinfunction "1_1") (pintype "passive"))
      (node (ref "C7") (pin "2") (pinfunction "2_2") (pintype "passive"))
      (node (ref "C8") (pin "2") (pinfunction "2_2") (pintype "passive"))
      (node (ref "C9") (pin "2") (pinfunction "2_2") (pintype "passive"))
      (node (ref "Cd1") (pin "1") (pinfunction "1_1") (pintype "passive"))
      (node (ref "Cd2") (pin "1") (pinfunction "1_1") (pintype "passive"))
      (node (ref "Cd3") (pin "1") (pinfunction "1_1") (pintype "passive"))
      (node (ref "Cd4") (pin "1") (pinfunction "1_1") (pintype "passive"))
      (node (ref "Cd5") (pin "1") (pinfunction "1_1") (pintype "passive"))
      (node (ref "Cd6") (pin "1") (pinfunction "1_1") (pintype "passive"))
      (node (ref "Cd7") (pin "1") (pinfunction "1_1") (pintype "passive"))
      (node (ref "Cd8") (pin "1") (pinfunction "1_1") (pintype "passive"))
      (node (ref "Cd9") (pin "1") (pinfunction "1_1") (pintype "passive"))
      (node (ref "ESP32 HiLetgo") (pin "16") (pinfunction "GND_16") (pintype "passive"))
      (node (ref "ESP32 HiLetgo") (pin "19") (pinfunction "GND_19") (pintype "passive"))
      (node (ref "ESP32 HiLetgo") (pin "29") (pinfunction "GND_29") (pintype "passive"))
      (node (ref "ESP32 HiLetgo") (pin "30") (pinfunction "GND_30") (pintype "passive"))
      (node (ref "ESP32 HiLetgo") (pin "36") (pinfunction "GND_36") (pintype "passive"))
      (node (ref "J1") (pin "1") (pinfunction "1_1") (pintype "passive"))
      (node (ref "J10") (pin "1") (pinfunction "1_1") (pintype "passive"))
      (node (ref "J11") (pin "1") (pinfunction "1_1") (pintype "passive"))
      (node (ref "J12") (pin "1") (pinfunction "1_1") (pintype "passive"))
      (node (ref "J13") (pin "1") (pinfunction "1_1") (pintype "passive"))
      (node (ref "J13") (pin "2") (pinfunction "2_2") (pintype "passive"))
      (node (ref "J2") (pin "1") (pinfunction "1_1") (pintype "passive"))
      (node (ref "J4") (pin "1") (pinfunction "1_1") (pintype "passive"))
      (node (ref "J5") (pin "1") (pinfunction "1_1") (pintype "passive"))
      (node (ref "J6") (pin "1") (pinfunction "1_1") (pintype "passive"))
      (node (ref "J7") (pin "1") (pinfunction "1_1") (pintype "passive"))
      (node (ref "J8") (pin "2") (pinfunction "2_2") (pintype "passive"))
      (node (ref "J8") (pin "3") (pinfunction "3_3") (pintype "passive"))
      (node (ref "J9") (pin "1") (pinfunction "1_1") (pintype "passive"))
      (node (ref "P1") (pin "5") (pinfunction "5_5") (pintype "passive"))
      (node (ref "P2") (pin "8") (pinfunction "8_8") (pintype "passive"))
      (node (ref "P_LED1") (pin "2") (pinfunction "K_2") (pintype "passive"))
      (node (ref "P_LED2") (pin "2") (pinfunction "K_2") (pintype "passive"))
      (node (ref "P_LED3") (pin "2") (pinfunction "K_2") (pintype "passive"))
      (node (ref "R12") (pin "2") (pinfunction "2_2") (pintype "passive"))
      (node (ref "SD1") (pin "11") (pinfunction "SHLD1_11") (pintype "passive"))
      (node (ref "SD1") (pin "12") (pinfunction "SHLD2_12") (pintype "passive"))
      (node (ref "SD1") (pin "6") (pinfunction "VSS2_6") (pintype "passive"))
      (node (ref "U1") (pin "10") (pinfunction "VSS_10") (pintype "power_in"))
      (node (ref "U1") (pin "20") (pinfunction "VSSA_20") (pintype "power_in"))
      (node (ref "U1") (pin "27") (pinfunction "VSS_27") (pintype "power_in"))
      (node (ref "U1") (pin "74") (pinfunction "VSS_74") (pintype "power_in"))
      (node (ref "U1") (pin "99") (pinfunction "VSS_99") (pintype "power_in"))
      (node (ref "U2") (pin "2") (pinfunction "GND_2") (pintype "power_in"))
      (node (ref "U2") (pin "4") (pinfunction "GND_4") (pintype "power_in"))
      (node (ref "U3") (pin "15") (pinfunction "GND_15") (pintype "power_in"))
      (node (ref "Y1") (pin "2") (pinfunction "GND_2") (pintype "power_in"))
      (node (ref "Y1") (pin "4") (pinfunction "GND_4") (pintype "power_in"))
    )
    (net (code "69") (name "unconnected-(ESP32 HiLetgoD-#EN-Pad2)") (class "Default")
      (node (ref "ESP32 HiLetgo") (pin "2") (pinfunction "#EN_2") (pintype "passive"))
    )
    (net (code "70") (name "unconnected-(ESP32 HiLetgoD-3v3-Pad1)") (class "Default")
      (node (ref "ESP32 HiLetgo") (pin "1") (pinfunction "3v3_1") (pintype "passive"))
    )
    (net (code "71") (name "unconnected-(ESP32 HiLetgoD-3v3-Pad24)") (class "Default")
      (node (ref "ESP32 HiLetgo") (pin "24") (pinfunction "3v3_24") (pintype "passive"))
    )
    (net (code "72") (name "unconnected-(ESP32 HiLetgoD-3v3-Pad33)") (class "Default")
      (node (ref "ESP32 HiLetgo") (pin "33") (pinfunction "3v3_33") (pintype "passive"))
    )
    (net (code "73") (name "unconnected-(ESP32 HiLetgoD-IO0-Pad20)") (class "Default")
      (node (ref "ESP32 HiLetgo") (pin "20") (pinfunction "IO0_20") (pintype "passive"))
    )
    (net (code "74") (name "unconnected-(ESP32 HiLetgoD-IO2-Pad18)") (class "Default")
      (node (ref "ESP32 HiLetgo") (pin "18") (pinfunction "IO2_18") (pintype "passive"))
    )
    (net (code "75") (name "unconnected-(ESP32 HiLetgoD-IO4-Pad21)") (class "Default")
      (node (ref "ESP32 HiLetgo") (pin "21") (pinfunction "IO4_21") (pintype "passive"))
    )
    (net (code "76") (name "unconnected-(ESP32 HiLetgoD-IO5-Pad25)") (class "Default")
      (node (ref "ESP32 HiLetgo") (pin "25") (pinfunction "IO5_25") (pintype "passive"))
    )
    (net (code "77") (name "unconnected-(ESP32 HiLetgoD-IO12-Pad13)") (class "Default")
      (node (ref "ESP32 HiLetgo") (pin "13") (pinfunction "IO12_13") (pintype "passive"))
    )
    (net (code "78") (name "unconnected-(ESP32 HiLetgoD-IO13-Pad14)") (class "Default")
      (node (ref "ESP32 HiLetgo") (pin "14") (pinfunction "IO13_14") (pintype "passive"))
    )
    (net (code "79") (name "unconnected-(ESP32 HiLetgoD-IO14-Pad12)") (class "Default")
      (node (ref "ESP32 HiLetgo") (pin "12") (pinfunction "IO14_12") (pintype "passive"))
    )
    (net (code "80") (name "unconnected-(ESP32 HiLetgoD-IO15-Pad17)") (class "Default")
      (node (ref "ESP32 HiLetgo") (pin "17") (pinfunction "IO15_17") (pintype "passive"))
    )
    (net (code "81") (name "unconnected-(ESP32 HiLetgoD-IO16-Pad22)") (class "Default")
      (node (ref "ESP32 HiLetgo") (pin "22") (pinfunction "IO16_22") (pintype "passive"))
    )
    (net (code "82") (name "unconnected-(ESP32 HiLetgoD-IO17-Pad23)") (class "Default")
      (node (ref "ESP32 HiLetgo") (pin "23") (pinfunction "IO17_23") (pintype "passive"))
    )
    (net (code "83") (name "unconnected-(ESP32 HiLetgoD-IO18-Pad26)") (class "Default")
      (node (ref "ESP32 HiLetgo") (pin "26") (pinfunction "IO18_26") (pintype "passive"))
    )
    (net (code "84") (name "unconnected-(ESP32 HiLetgoD-IO19-Pad28)") (class "Default")
      (node (ref "ESP32 HiLetgo") (pin "28") (pinfunction "IO19_28") (pintype "passive"))
    )
    (net (code "85") (name "unconnected-(ESP32 HiLetgoD-IO23-Pad27)") (class "Default")
      (node (ref "ESP32 HiLetgo") (pin "27") (pinfunction "IO23_27") (pintype "passive"))
    )
    (net (code "86") (name "unconnected-(ESP32 HiLetgoD-IO25-Pad9)") (class "Default")
      (node (ref "ESP32 HiLetgo") (pin "9") (pinfunction "IO25_9") (pintype "passive"))
    )
    (net (code "87") (name "unconnected-(ESP32 HiLetgoD-IO26-Pad10)") (class "Default")
      (node (ref "ESP32 HiLetgo") (pin "10") (pinfunction "IO26_10") (pintype "passive"))
    )
    (net (code "88") (name "unconnected-(ESP32 HiLetgoD-IO27-Pad11)") (class "Default")
      (node (ref "ESP32 HiLetgo") (pin "11") (pinfunction "IO27_11") (pintype "passive"))
    )
    (net (code "89") (name "unconnected-(ESP32 HiLetgoD-IO32-Pad5)") (class "Default")
      (node (ref "ESP32 HiLetgo") (pin "5") (pinfunction "IO32_5") (pintype "passive"))
    )
    (net (code "90") (name "unconnected-(ESP32 HiLetgoD-IO33-Pad6)") (class "Default")
      (node (ref "ESP32 HiLetgo") (pin "6") (pinfunction "IO33_6") (pintype "passive"))
    )
    (net (code "91") (name "unconnected-(ESP32 HiLetgoD-IO34-Pad7)") (class "Default")
      (node (ref "ESP32 HiLetgo") (pin "7") (pinfunction "IO34_7") (pintype "passive"))
    )
    (net (code "92") (name "unconnected-(ESP32 HiLetgoD-IO35-Pad8)") (class "Default")
      (node (ref "ESP32 HiLetgo") (pin "8") (pinfunction "IO35_8") (pintype "passive"))
    )
    (net (code "93") (name "unconnected-(ESP32 HiLetgoD-SCL-Pad32)") (class "Default")
      (node (ref "ESP32 HiLetgo") (pin "32") (pinfunction "SCL_32") (pintype "passive"))
    )
    (net (code "94") (name "unconnected-(ESP32 HiLetgoD-SDA-Pad31)") (class "Default")
      (node (ref "ESP32 HiLetgo") (pin "31") (pinfunction "SDA_31") (pintype "passive"))
    )
    (net (code "95") (name "unconnected-(ESP32 HiLetgoD-SVN-Pad4)") (class "Default")
      (node (ref "ESP32 HiLetgo") (pin "4") (pinfunction "SVN_4") (pintype "passive"))
    )
    (net (code "96") (name "unconnected-(ESP32 HiLetgoD-SVP-Pad3)") (class "Default")
      (node (ref "ESP32 HiLetgo") (pin "3") (pinfunction "SVP_3") (pintype "passive"))
    )
    (net (code "97") (name "unconnected-(H1-Pad0)") (class "Default")
      (node (ref "H1") (pin "0") (pinfunction "0_0") (pintype "passive"))
    )
    (net (code "98") (name "unconnected-(H2-Pad0)") (class "Default")
      (node (ref "H2") (pin "0") (pinfunction "0_0") (pintype "passive"))
    )
    (net (code "99") (name "unconnected-(H3-Pad0)") (class "Default")
      (node (ref "H3") (pin "0") (pinfunction "0_0") (pintype "passive"))
    )
    (net (code "100") (name "unconnected-(J10-Pad4)") (class "Default")
      (node (ref "J10") (pin "4") (pinfunction "4_4") (pintype "passive"))
    )
    (net (code "101") (name "unconnected-(U1A-PA2-Pad25)") (class "Default")
      (node (ref "U1") (pin "25") (pinfunction "PA2_25") (pintype "bidirectional"))
    )
    (net (code "102") (name "unconnected-(U1A-PA8-Pad67)") (class "Default")
      (node (ref "U1") (pin "67") (pinfunction "PA8_67") (pintype "bidirectional"))
    )
    (net (code "103") (name "unconnected-(U1A-PA9-Pad68)") (class "Default")
      (node (ref "U1") (pin "68") (pinfunction "PA9_68") (pintype "bidirectional"))
    )
    (net (code "104") (name "unconnected-(U1A-PA10-Pad69)") (class "Default")
      (node (ref "U1") (pin "69") (pinfunction "PA10_69") (pintype "bidirectional"))
    )
    (net (code "105") (name "unconnected-(U1A-PA11-Pad70)") (class "Default")
      (node (ref "U1") (pin "70") (pinfunction "PA11_70") (pintype "bidirectional"))
    )
    (net (code "106") (name "unconnected-(U1A-PA12-Pad71)") (class "Default")
      (node (ref "U1") (pin "71") (pinfunction "PA12_71") (pintype "bidirectional"))
    )
    (net (code "107") (name "unconnected-(U1A-PA15(JTDI)-Pad77)") (class "Default")
      (node (ref "U1") (pin "77") (pinfunction "PA15(JTDI)_77") (pintype "bidirectional"))
    )
    (net (code "108") (name "unconnected-(U1A-PB1-Pad36)") (class "Default")
      (node (ref "U1") (pin "36") (pinfunction "PB1_36") (pintype "bidirectional"))
    )
    (net (code "109") (name "unconnected-(U1A-PB2{slash}BOOT1(PB2)-Pad37)") (class "Default")
      (node (ref "U1") (pin "37") (pinfunction "PB2/BOOT1(PB2)_37") (pintype "bidirectional"))
    )
    (net (code "110") (name "unconnected-(U1A-PB4(NJTRST)-Pad90)") (class "Default")
      (node (ref "U1") (pin "90") (pinfunction "PB4(NJTRST)_90") (pintype "bidirectional"))
    )
    (net (code "111") (name "unconnected-(U1A-PB5-Pad91)") (class "Default")
      (node (ref "U1") (pin "91") (pinfunction "PB5_91") (pintype "bidirectional"))
    )
    (net (code "112") (name "unconnected-(U1A-PB8-Pad95)") (class "Default")
      (node (ref "U1") (pin "95") (pinfunction "PB8_95") (pintype "bidirectional"))
    )
    (net (code "113") (name "unconnected-(U1A-PB9-Pad96)") (class "Default")
      (node (ref "U1") (pin "96") (pinfunction "PB9_96") (pintype "bidirectional"))
    )
    (net (code "114") (name "unconnected-(U1A-PB12-Pad51)") (class "Default")
      (node (ref "U1") (pin "51") (pinfunction "PB12_51") (pintype "bidirectional"))
    )
    (net (code "115") (name "unconnected-(U1A-PB13-Pad52)") (class "Default")
      (node (ref "U1") (pin "52") (pinfunction "PB13_52") (pintype "bidirectional"))
    )
    (net (code "116") (name "unconnected-(U1A-PB14-Pad53)") (class "Default")
      (node (ref "U1") (pin "53") (pinfunction "PB14_53") (pintype "bidirectional"))
    )
    (net (code "117") (name "unconnected-(U1A-PB15-Pad54)") (class "Default")
      (node (ref "U1") (pin "54") (pinfunction "PB15_54") (pintype "bidirectional"))
    )
    (net (code "118") (name "unconnected-(U1A-PC0-Pad15)") (class "Default")
      (node (ref "U1") (pin "15") (pinfunction "PC0_15") (pintype "bidirectional"))
    )
    (net (code "119") (name "unconnected-(U1A-PC1-Pad16)") (class "Default")
      (node (ref "U1") (pin "16") (pinfunction "PC1_16") (pintype "bidirectional"))
    )
    (net (code "120") (name "unconnected-(U1A-PC2-Pad17)") (class "Default")
      (node (ref "U1") (pin "17") (pinfunction "PC2_17") (pintype "bidirectional"))
    )
    (net (code "121") (name "unconnected-(U1A-PC3-Pad18)") (class "Default")
      (node (ref "U1") (pin "18") (pinfunction "PC3_18") (pintype "bidirectional"))
    )
    (net (code "122") (name "unconnected-(U1A-PC4-Pad33)") (class "Default")
      (node (ref "U1") (pin "33") (pinfunction "PC4_33") (pintype "bidirectional"))
    )
    (net (code "123") (name "unconnected-(U1A-PC5-Pad34)") (class "Default")
      (node (ref "U1") (pin "34") (pinfunction "PC5_34") (pintype "bidirectional"))
    )
    (net (code "124") (name "unconnected-(U1A-PC13-Pad7)") (class "Default")
      (node (ref "U1") (pin "7") (pinfunction "PC13_7") (pintype "bidirectional"))
    )
    (net (code "125") (name "unconnected-(U1A-PD0-Pad81)") (class "Default")
      (node (ref "U1") (pin "81") (pinfunction "PD0_81") (pintype "bidirectional"))
    )
    (net (code "126") (name "unconnected-(U1A-PD1-Pad82)") (class "Default")
      (node (ref "U1") (pin "82") (pinfunction "PD1_82") (pintype "bidirectional"))
    )
    (net (code "127") (name "unconnected-(U1A-PD4-Pad85)") (class "Default")
      (node (ref "U1") (pin "85") (pinfunction "PD4_85") (pintype "bidirectional"))
    )
    (net (code "128") (name "unconnected-(U1A-PD7-Pad88)") (class "Default")
      (node (ref "U1") (pin "88") (pinfunction "PD7_88") (pintype "bidirectional"))
    )
    (net (code "129") (name "unconnected-(U1A-PD8-Pad55)") (class "Default")
      (node (ref "U1") (pin "55") (pinfunction "PD8_55") (pintype "bidirectional"))
    )
    (net (code "130") (name "unconnected-(U1A-PD12-Pad59)") (class "Default")
      (node (ref "U1") (pin "59") (pinfunction "PD12_59") (pintype "bidirectional"))
    )
    (net (code "131") (name "unconnected-(U1A-PD13-Pad60)") (class "Default")
      (node (ref "U1") (pin "60") (pinfunction "PD13_60") (pintype "bidirectional"))
    )
    (net (code "132") (name "unconnected-(U1A-PD14-Pad61)") (class "Default")
      (node (ref "U1") (pin "61") (pinfunction "PD14_61") (pintype "bidirectional"))
    )
    (net (code "133") (name "unconnected-(U1A-PD15-Pad62)") (class "Default")
      (node (ref "U1") (pin "62") (pinfunction "PD15_62") (pintype "bidirectional"))
    )
    (net (code "134") (name "unconnected-(U1A-PE0-Pad97)") (class "Default")
      (node (ref "U1") (pin "97") (pinfunction "PE0_97") (pintype "bidirectional"))
    )
    (net (code "135") (name "unconnected-(U1A-PE1-Pad98)") (class "Default")
      (node (ref "U1") (pin "98") (pinfunction "PE1_98") (pintype "bidirectional"))
    )
    (net (code "136") (name "unconnected-(U1A-PE7-Pad38)") (class "Default")
      (node (ref "U1") (pin "38") (pinfunction "PE7_38") (pintype "bidirectional"))
    )
    (net (code "137") (name "unconnected-(U1A-PE14-Pad45)") (class "Default")
      (node (ref "U1") (pin "45") (pinfunction "PE14_45") (pintype "bidirectional"))
    )
    (net (code "138") (name "unconnected-(U1A-PE15-Pad46)") (class "Default")
      (node (ref "U1") (pin "46") (pinfunction "PE15_46") (pintype "bidirectional"))
    )
    (net (code "139") (name "unconnected-(U3-DIN2-Pad10)") (class "Default")
      (node (ref "U3") (pin "10") (pinfunction "DIN2_10") (pintype "input"))
    )
    (net (code "140") (name "unconnected-(U3-DOUT2-Pad7)") (class "Default")
      (node (ref "U3") (pin "7") (pinfunction "DOUT2_7") (pintype "output"))
    )
    (net (code "141") (name "unconnected-(U3-RIN2-Pad8)") (class "Default")
      (node (ref "U3") (pin "8") (pinfunction "RIN2_8") (pintype "input"))
    )
    (net (code "142") (name "unconnected-(U3-ROUT2-Pad9)") (class "Default")
      (node (ref "U3") (pin "9") (pinfunction "ROUT2_9") (pintype "output"))
    )
    (net (code "143") (name "unconnected-(Y2-NC-Pad2)") (class "Default")
      (node (ref "Y2") (pin "2") (pinfunction "NC_2") (pintype "passive"))
    )
    (net (code "144") (name "unconnected-(Y2-NC-Pad3)") (class "Default")
      (node (ref "Y2") (pin "3") (pinfunction "NC_3") (pintype "passive"))
    )
  )
)
